# Arduino_FPGA_Top-Level_Interface.net
KiCad netlist of a schematic drawn in Altium Designer
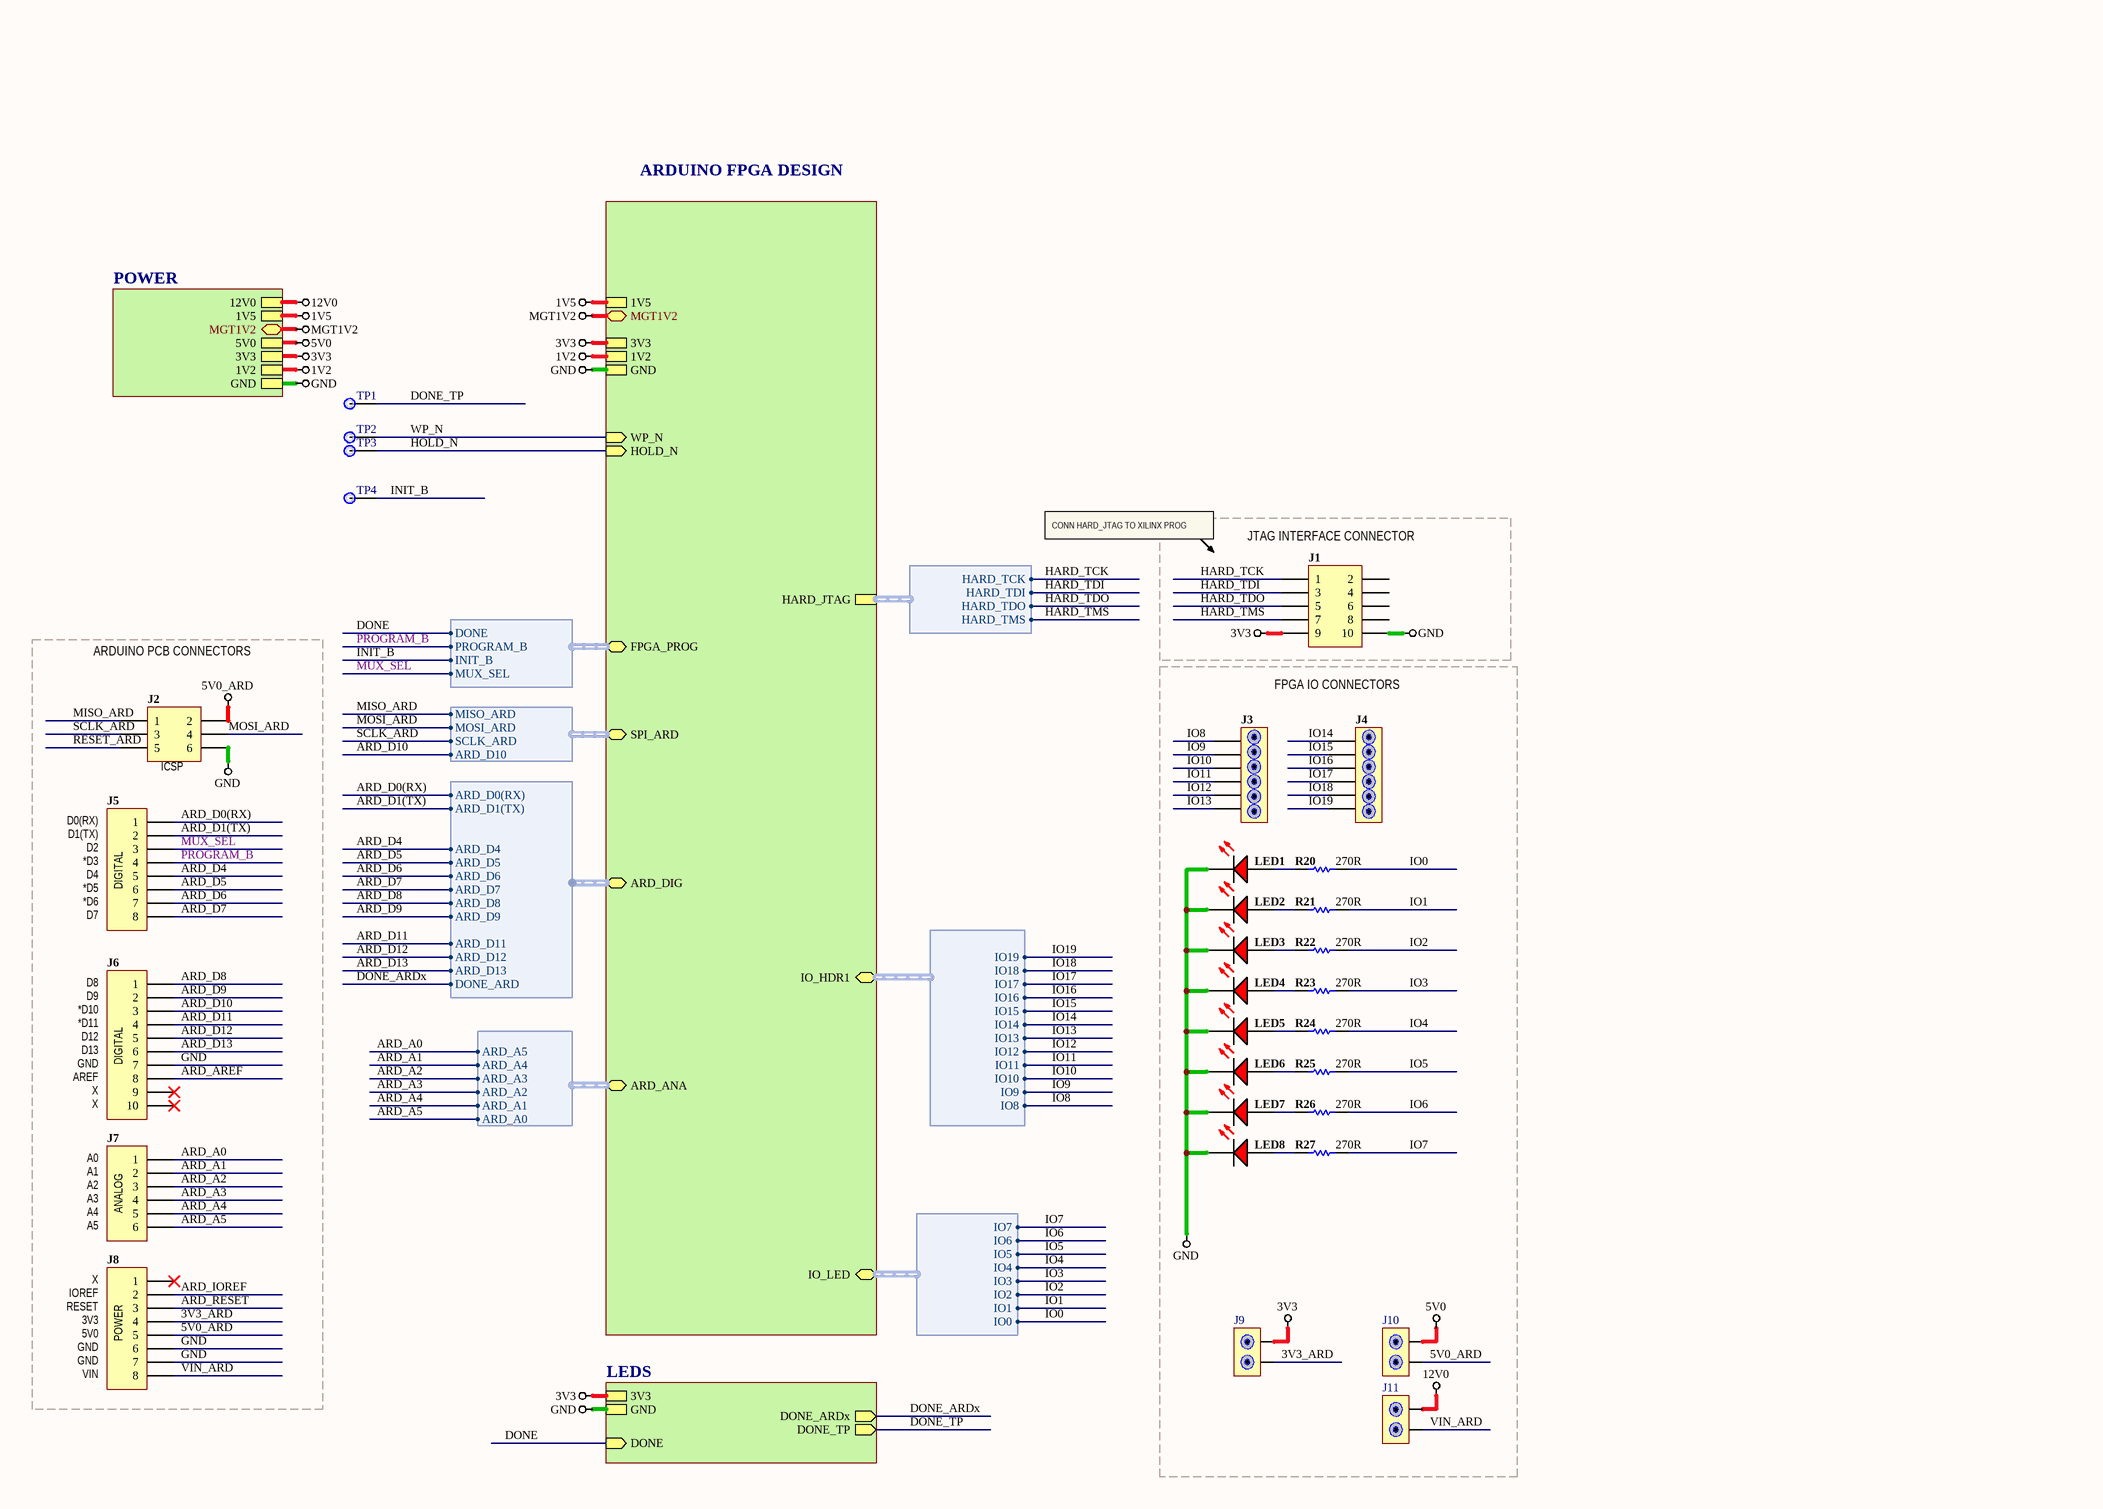
[diagram p0: Arduino FPGA Top-Level Interface.SchDoc]

(export (version "E")
  (design (tool "Eeschema 10.0.6"))
  (components
    (comp (ref "J1")
      (value "Header 5X2")
      (footprint "HDR2X5")
      (description "Header, 5-Pin, Dual row")
      (fields
        (field (name "MANUFACTURER PART NUMBER") "67997-210HLF")
        (field (name "PUBLISHER") "Altium Limited")
      )
      (libsource (lib "Miscellaneous Connectors") (part "Header 5X2"))
    )
    (comp (ref "J2")
      (value "Header 3X2")
      (footprint "2X03")
      (description "Header, 3-Pin, Dual row")
      (fields (field (name "MANUFACTURER PART NUMBER") "DNP") (field (name "PUBLISHER") "Altium Limited"))
      (libsource (lib "Miscellaneous Connectors") (part "Header 3X2"))
    )
    (comp (ref "J3")
      (value "6-POS VERTICAL HEADER")
      (footprint "HDR1X6")
      (fields (field (name "MANUFACTURER PART NUMBER") "68000-406HLF"))
      (libsource (lib "HDR1X6") (part "6-POS-HDR"))
    )
    (comp (ref "J4")
      (value "6-POS VERTICAL HEADER")
      (footprint "HDR1X6")
      (fields (field (name "MANUFACTURER PART NUMBER") "68000-406HLF"))
      (libsource (lib "HDR1X6") (part "6-POS-HDR"))
    )
    (comp (ref "J5")
      (value "Header 8")
      (footprint "1X08")
      (description "Header, 8-Pin")
      (fields (field (name "MANUFACTURER PART NUMBER") "DNP") (field (name "PUBLISHER") "Altium Limited"))
      (libsource (lib "Miscellaneous Connectors") (part "Header 8"))
    )
    (comp (ref "J6")
      (value "Header 10")
      (footprint "1X10@1")
      (description "Header, 10-Pin")
      (fields (field (name "MANUFACTURER PART NUMBER") "DNP") (field (name "PUBLISHER") "Altium Limited"))
      (libsource (lib "Miscellaneous Connectors") (part "Header 10"))
    )
    (comp (ref "J7")
      (value "Header 6")
      (footprint "1X06")
      (description "Header, 6-Pin")
      (fields (field (name "MANUFACTURER PART NUMBER") "DNP") (field (name "PUBLISHER") "Altium Limited"))
      (libsource (lib "Miscellaneous Connectors") (part "Header 6"))
    )
    (comp (ref "J8")
      (value "Header 8")
      (footprint "1X08")
      (description "Header, 8-Pin")
      (fields (field (name "MANUFACTURER PART NUMBER") "DNP") (field (name "PUBLISHER") "Altium Limited"))
      (libsource (lib "Miscellaneous Connectors") (part "Header 8"))
    )
    (comp (ref "J9")
      (value "Jumper")
      (footprint "JMP1X2")
      (description "Standard 2 Pin Jumper, 100mil spacing")
      (fields (field (name "MANUFACTURER PART NUMBER") "M20-9770246"))
      (libsource (lib "JMP1X2") (part "JMP1X2"))
    )
    (comp (ref "J10")
      (value "Jumper")
      (footprint "JMP1X2")
      (description "Standard 2 Pin Jumper, 100mil spacing")
      (fields (field (name "MANUFACTURER PART NUMBER") "M20-9770246"))
      (libsource (lib "JMP1X2") (part "JMP1X2"))
    )
    (comp (ref "J11")
      (value "Jumper")
      (footprint "JMP1X2")
      (description "Standard 2 Pin Jumper, 100mil spacing")
      (fields (field (name "MANUFACTURER PART NUMBER") "M20-9770246"))
      (libsource (lib "JMP1X2") (part "JMP1X2"))
    )
    (comp (ref "LED1")
      (value "0402-LED-RED")
      (footprint "LED_0402")
      (description "0402 LED,RED")
      (fields (field (name "MANUFACTURER PART NUMBER") "LTST-C190KRKT"))
      (libsource (lib "Component_DB") (part "LED_RED_A1K2-2"))
    )
    (comp (ref "LED2")
      (value "0402-LED-RED")
      (footprint "LED_0402")
      (description "0402 LED,RED")
      (fields (field (name "MANUFACTURER PART NUMBER") "LTST-C190KRKT"))
      (libsource (lib "Component_DB") (part "LED_RED_A1K2-2"))
    )
    (comp (ref "LED3")
      (value "0402-LED-RED")
      (footprint "LED_0402")
      (description "0402 LED,RED")
      (fields (field (name "MANUFACTURER PART NUMBER") "LTST-C190KRKT"))
      (libsource (lib "Component_DB") (part "LED_RED_A1K2-2"))
    )
    (comp (ref "LED4")
      (value "0402-LED-RED")
      (footprint "LED_0402")
      (description "0402 LED,RED")
      (fields (field (name "MANUFACTURER PART NUMBER") "LTST-C190KRKT"))
      (libsource (lib "Component_DB") (part "LED_RED_A1K2-2"))
    )
    (comp (ref "LED5")
      (value "0402-LED-RED")
      (footprint "LED_0402")
      (description "0402 LED,RED")
      (fields (field (name "MANUFACTURER PART NUMBER") "LTST-C190KRKT"))
      (libsource (lib "Component_DB") (part "LED_RED_A1K2-2"))
    )
    (comp (ref "LED6")
      (value "0402-LED-RED")
      (footprint "LED_0402")
      (description "0402 LED,RED")
      (fields (field (name "MANUFACTURER PART NUMBER") "LTST-C190KRKT"))
      (libsource (lib "Component_DB") (part "LED_RED_A1K2-2"))
    )
    (comp (ref "LED7")
      (value "0402-LED-RED")
      (footprint "LED_0402")
      (description "0402 LED,RED")
      (fields (field (name "MANUFACTURER PART NUMBER") "LTST-C190KRKT"))
      (libsource (lib "Component_DB") (part "LED_RED_A1K2-2"))
    )
    (comp (ref "LED8")
      (value "0402-LED-RED")
      (footprint "LED_0402")
      (description "0402 LED,RED")
      (fields (field (name "MANUFACTURER PART NUMBER") "LTST-C190KRKT"))
      (libsource (lib "Component_DB") (part "LED_RED_A1K2-2"))
    )
    (comp (ref "R20")
      (value "270R")
      (footprint "RESC0402(1005)40_L")
      (description "0402 (1005 Metric) 1/16 W 270R 1 Thick Film Chip Resistor")
      (fields (field (name "POWER") "1/16 W") (field (name "MANUFACTURER PART NUMBER") "RC1005F271CS"))
      (libsource (lib "Component_DB") (part "RES"))
    )
    (comp (ref "R21")
      (value "270R")
      (footprint "RESC0402(1005)40_L")
      (description "0402 (1005 Metric) 1/16 W 270R 1 Thick Film Chip Resistor")
      (fields (field (name "POWER") "1/16 W") (field (name "MANUFACTURER PART NUMBER") "RC1005F271CS"))
      (libsource (lib "Component_DB") (part "RES"))
    )
    (comp (ref "R22")
      (value "270R")
      (footprint "RESC0402(1005)40_L")
      (description "0402 (1005 Metric) 1/16 W 270R 1 Thick Film Chip Resistor")
      (fields (field (name "POWER") "1/16 W") (field (name "MANUFACTURER PART NUMBER") "RC1005F271CS"))
      (libsource (lib "Component_DB") (part "RES"))
    )
    (comp (ref "R23")
      (value "270R")
      (footprint "RESC0402(1005)40_L")
      (description "0402 (1005 Metric) 1/16 W 270R 1 Thick Film Chip Resistor")
      (fields (field (name "POWER") "1/16 W") (field (name "MANUFACTURER PART NUMBER") "RC1005F271CS"))
      (libsource (lib "Component_DB") (part "RES"))
    )
    (comp (ref "R24")
      (value "270R")
      (footprint "RESC0402(1005)40_L")
      (description "0402 (1005 Metric) 1/16 W 270R 1 Thick Film Chip Resistor")
      (fields (field (name "POWER") "1/16 W") (field (name "MANUFACTURER PART NUMBER") "RC1005F271CS"))
      (libsource (lib "Component_DB") (part "RES"))
    )
    (comp (ref "R25")
      (value "270R")
      (footprint "RESC0402(1005)40_L")
      (description "0402 (1005 Metric) 1/16 W 270R 1 Thick Film Chip Resistor")
      (fields (field (name "POWER") "1/16 W") (field (name "MANUFACTURER PART NUMBER") "RC1005F271CS"))
      (libsource (lib "Component_DB") (part "RES"))
    )
    (comp (ref "R26")
      (value "270R")
      (footprint "RESC0402(1005)40_L")
      (description "0402 (1005 Metric) 1/16 W 270R 1 Thick Film Chip Resistor")
      (fields (field (name "POWER") "1/16 W") (field (name "MANUFACTURER PART NUMBER") "RC1005F271CS"))
      (libsource (lib "Component_DB") (part "RES"))
    )
    (comp (ref "R27")
      (value "270R")
      (footprint "RESC0402(1005)40_L")
      (description "0402 (1005 Metric) 1/16 W 270R 1 Thick Film Chip Resistor")
      (fields (field (name "POWER") "1/16 W") (field (name "MANUFACTURER PART NUMBER") "RC1005F271CS"))
      (libsource (lib "Component_DB") (part "RES"))
    )
    (comp (ref "TP1")
      (value "TESTPOINT_TH")
      (footprint "TESTPOINT_TH")
      (fields (field (name "MANUFACTURER PART NUMBER") "TESTPOINT"))
      (libsource (lib "TESTPOINT_TH") (part "TESTPOINT_TH"))
    )
    (comp (ref "TP2")
      (value "TESTPOINT_TH")
      (footprint "TESTPOINT_TH")
      (fields (field (name "MANUFACTURER PART NUMBER") "TESTPOINT"))
      (libsource (lib "TESTPOINT_TH") (part "TESTPOINT_TH"))
    )
    (comp (ref "TP3")
      (value "TESTPOINT_TH")
      (footprint "TESTPOINT_TH")
      (fields (field (name "MANUFACTURER PART NUMBER") "TESTPOINT"))
      (libsource (lib "TESTPOINT_TH") (part "TESTPOINT_TH"))
    )
    (comp (ref "TP4")
      (value "TESTPOINT_TH")
      (footprint "TESTPOINT_TH")
      (fields (field (name "MANUFACTURER PART NUMBER") "TESTPOINT"))
      (libsource (lib "TESTPOINT_TH") (part "TESTPOINT_TH"))
    )
  )
  (nets
    (net (code "8") (name "/3V3_ARD") (class "Default")
      (node (ref "J8") (pin "4") (pinfunction "4_4") (pintype "passive"))
      (node (ref "J9") (pin "1") (pinfunction "1_1") (pintype "passive"))
    )
    (net (code "9") (name "/ARD_A0") (class "Default")
      (node (ref "J7") (pin "1") (pinfunction "1_1") (pintype "passive"))
    )
    (net (code "10") (name "/ARD_A1") (class "Default")
      (node (ref "J7") (pin "2") (pinfunction "2_2") (pintype "passive"))
    )
    (net (code "11") (name "/ARD_A2") (class "Default")
      (node (ref "J7") (pin "3") (pinfunction "3_3") (pintype "passive"))
    )
    (net (code "12") (name "/ARD_A3") (class "Default")
      (node (ref "J7") (pin "4") (pinfunction "4_4") (pintype "passive"))
    )
    (net (code "13") (name "/ARD_A4") (class "Default")
      (node (ref "J7") (pin "5") (pinfunction "5_5") (pintype "passive"))
    )
    (net (code "14") (name "/ARD_A5") (class "Default")
      (node (ref "J7") (pin "6") (pinfunction "6_6") (pintype "passive"))
    )
    (net (code "15") (name "/ARD_AREF") (class "Default")
      (node (ref "J6") (pin "8") (pinfunction "8_8") (pintype "passive"))
    )
    (net (code "16") (name "/ARD_D0(RX)") (class "Default")
      (node (ref "J5") (pin "1") (pinfunction "1_1") (pintype "passive"))
    )
    (net (code "17") (name "/ARD_D1(TX)") (class "Default")
      (node (ref "J5") (pin "2") (pinfunction "2_2") (pintype "passive"))
    )
    (net (code "18") (name "/ARD_D4") (class "Default")
      (node (ref "J5") (pin "5") (pinfunction "5_5") (pintype "passive"))
    )
    (net (code "19") (name "/ARD_D5") (class "Default")
      (node (ref "J5") (pin "6") (pinfunction "6_6") (pintype "passive"))
    )
    (net (code "20") (name "/ARD_D6") (class "Default")
      (node (ref "J5") (pin "7") (pinfunction "7_7") (pintype "passive"))
    )
    (net (code "21") (name "/ARD_D7") (class "Default")
      (node (ref "J5") (pin "8") (pinfunction "8_8") (pintype "passive"))
    )
    (net (code "22") (name "/ARD_D8") (class "Default")
      (node (ref "J6") (pin "1") (pinfunction "1_1") (pintype "passive"))
    )
    (net (code "23") (name "/ARD_D9") (class "Default")
      (node (ref "J6") (pin "2") (pinfunction "2_2") (pintype "passive"))
    )
    (net (code "24") (name "/ARD_D10") (class "Default")
      (node (ref "J6") (pin "3") (pinfunction "3_3") (pintype "passive"))
    )
    (net (code "25") (name "/ARD_D11") (class "Default")
      (node (ref "J6") (pin "4") (pinfunction "4_4") (pintype "passive"))
    )
    (net (code "26") (name "/ARD_D12") (class "Default")
      (node (ref "J6") (pin "5") (pinfunction "5_5") (pintype "passive"))
    )
    (net (code "27") (name "/ARD_D13") (class "Default")
      (node (ref "J6") (pin "6") (pinfunction "6_6") (pintype "passive"))
    )
    (net (code "28") (name "/ARD_IOREF") (class "Default")
      (node (ref "J8") (pin "2") (pinfunction "2_2") (pintype "passive"))
    )
    (net (code "29") (name "/ARD_RESET") (class "Default")
      (node (ref "J8") (pin "3") (pinfunction "3_3") (pintype "passive"))
    )
    (net (code "32") (name "/DONE_TP") (class "Default")
      (node (ref "TP1") (pin "1") (pinfunction "1_1") (pintype "passive"))
    )
    (net (code "33") (name "/HARD_TCK") (class "Default")
      (node (ref "J1") (pin "1") (pinfunction "1_1") (pintype "passive"))
    )
    (net (code "34") (name "/HARD_TDI") (class "Default")
      (node (ref "J1") (pin "3") (pinfunction "3_3") (pintype "passive"))
    )
    (net (code "35") (name "/HARD_TDO") (class "Default")
      (node (ref "J1") (pin "5") (pinfunction "5_5") (pintype "passive"))
    )
    (net (code "36") (name "/HARD_TMS") (class "Default")
      (node (ref "J1") (pin "7") (pinfunction "7_7") (pintype "passive"))
    )
    (net (code "37") (name "/HOLD_N") (class "Default")
      (node (ref "TP3") (pin "1") (pinfunction "1_1") (pintype "passive"))
    )
    (net (code "38") (name "/INIT_B") (class "Default")
      (node (ref "TP4") (pin "1") (pinfunction "1_1") (pintype "passive"))
    )
    (net (code "39") (name "/IO0") (class "Default")
      (node (ref "R20") (pin "2") (pinfunction "2_2") (pintype "passive"))
    )
    (net (code "40") (name "/IO1") (class "Default")
      (node (ref "R21") (pin "2") (pinfunction "2_2") (pintype "passive"))
    )
    (net (code "41") (name "/IO2") (class "Default")
      (node (ref "R22") (pin "2") (pinfunction "2_2") (pintype "passive"))
    )
    (net (code "42") (name "/IO3") (class "Default")
      (node (ref "R23") (pin "2") (pinfunction "2_2") (pintype "passive"))
    )
    (net (code "43") (name "/IO4") (class "Default")
      (node (ref "R24") (pin "2") (pinfunction "2_2") (pintype "passive"))
    )
    (net (code "44") (name "/IO5") (class "Default")
      (node (ref "R25") (pin "2") (pinfunction "2_2") (pintype "passive"))
    )
    (net (code "45") (name "/IO6") (class "Default")
      (node (ref "R26") (pin "2") (pinfunction "2_2") (pintype "passive"))
    )
    (net (code "46") (name "/IO7") (class "Default")
      (node (ref "R27") (pin "2") (pinfunction "2_2") (pintype "passive"))
    )
    (net (code "47") (name "/IO8") (class "Default")
      (node (ref "J3") (pin "1") (pinfunction "1_1") (pintype "passive"))
    )
    (net (code "48") (name "/IO9") (class "Default")
      (node (ref "J3") (pin "2") (pinfunction "2_2") (pintype "passive"))
    )
    (net (code "49") (name "/IO10") (class "Default")
      (node (ref "J3") (pin "3") (pinfunction "3_3") (pintype "passive"))
    )
    (net (code "50") (name "/IO11") (class "Default")
      (node (ref "J3") (pin "4") (pinfunction "4_4") (pintype "passive"))
    )
    (net (code "51") (name "/IO12") (class "Default")
      (node (ref "J3") (pin "5") (pinfunction "5_5") (pintype "passive"))
    )
    (net (code "52") (name "/IO13") (class "Default")
      (node (ref "J3") (pin "6") (pinfunction "6_6") (pintype "passive"))
    )
    (net (code "53") (name "/IO14") (class "Default")
      (node (ref "J4") (pin "1") (pinfunction "1_1") (pintype "passive"))
    )
    (net (code "54") (name "/IO15") (class "Default")
      (node (ref "J4") (pin "2") (pinfunction "2_2") (pintype "passive"))
    )
    (net (code "55") (name "/IO16") (class "Default")
      (node (ref "J4") (pin "3") (pinfunction "3_3") (pintype "passive"))
    )
    (net (code "56") (name "/IO17") (class "Default")
      (node (ref "J4") (pin "4") (pinfunction "4_4") (pintype "passive"))
    )
    (net (code "57") (name "/IO18") (class "Default")
      (node (ref "J4") (pin "5") (pinfunction "5_5") (pintype "passive"))
    )
    (net (code "58") (name "/IO19") (class "Default")
      (node (ref "J4") (pin "6") (pinfunction "6_6") (pintype "passive"))
    )
    (net (code "59") (name "/MISO_ARD") (class "Default")
      (node (ref "J2") (pin "1") (pinfunction "1_1") (pintype "passive"))
    )
    (net (code "60") (name "/MOSI_ARD") (class "Default")
      (node (ref "J2") (pin "4") (pinfunction "4_4") (pintype "passive"))
    )
    (net (code "61") (name "/MUX_SEL") (class "Default")
      (node (ref "J5") (pin "3") (pinfunction "3_3") (pintype "passive"))
    )
    (net (code "62") (name "/PROGRAM_B") (class "Default")
      (node (ref "J5") (pin "4") (pinfunction "4_4") (pintype "passive"))
    )
    (net (code "63") (name "/RESET_ARD") (class "Default")
      (node (ref "J2") (pin "5") (pinfunction "5_5") (pintype "passive"))
    )
    (net (code "64") (name "/SCLK_ARD") (class "Default")
      (node (ref "J2") (pin "3") (pinfunction "3_3") (pintype "passive"))
    )
    (net (code "65") (name "/VIN_ARD") (class "Default")
      (node (ref "J11") (pin "1") (pinfunction "1_1") (pintype "passive"))
      (node (ref "J8") (pin "8") (pinfunction "8_8") (pintype "passive"))
    )
    (net (code "66") (name "/WP_N") (class "Default")
      (node (ref "TP2") (pin "1") (pinfunction "1_1") (pintype "passive"))
    )
    (net (code "76") (name "3V3") (class "Default")
      (node (ref "J1") (pin "9") (pinfunction "9_9") (pintype "passive"))
      (node (ref "J9") (pin "2") (pinfunction "2_2") (pintype "passive"))
    )
    (net (code "77") (name "5V0") (class "Default")
      (node (ref "J10") (pin "2") (pinfunction "2_2") (pintype "passive"))
    )
    (net (code "78") (name "5V0_ARD") (class "Default")
      (node (ref "J10") (pin "1") (pinfunction "1_1") (pintype "passive"))
      (node (ref "J8") (pin "5") (pinfunction "5_5") (pintype "passive"))
    )
    (net (code "79") (name "12V0") (class "Default")
      (node (ref "J11") (pin "2") (pinfunction "2_2") (pintype "passive"))
    )
    (net (code "80") (name "GND") (class "Default")
      (node (ref "J1") (pin "10") (pinfunction "10_10") (pintype "passive"))
      (node (ref "J2") (pin "6") (pinfunction "6_6") (pintype "passive"))
      (node (ref "J6") (pin "7") (pinfunction "7_7") (pintype "passive"))
      (node (ref "J8") (pin "6") (pinfunction "6_6") (pintype "passive"))
      (node (ref "J8") (pin "7") (pinfunction "7_7") (pintype "passive"))
      (node (ref "LED1") (pin "2") (pinfunction "K_2") (pintype "passive"))
      (node (ref "LED2") (pin "2") (pinfunction "K_2") (pintype "passive"))
      (node (ref "LED3") (pin "2") (pinfunction "K_2") (pintype "passive"))
      (node (ref "LED4") (pin "2") (pinfunction "K_2") (pintype "passive"))
      (node (ref "LED5") (pin "2") (pinfunction "K_2") (pintype "passive"))
      (node (ref "LED6") (pin "2") (pinfunction "K_2") (pintype "passive"))
      (node (ref "LED7") (pin "2") (pinfunction "K_2") (pintype "passive"))
      (node (ref "LED8") (pin "2") (pinfunction "K_2") (pintype "passive"))
    )
    (net (code "82") (name "Net-(LED1-A)") (class "Default")
      (node (ref "LED1") (pin "1") (pinfunction "A_1") (pintype "passive"))
      (node (ref "R20") (pin "1") (pinfunction "1_1") (pintype "passive"))
    )
    (net (code "83") (name "Net-(LED2-A)") (class "Default")
      (node (ref "LED2") (pin "1") (pinfunction "A_1") (pintype "passive"))
      (node (ref "R21") (pin "1") (pinfunction "1_1") (pintype "passive"))
    )
    (net (code "84") (name "Net-(LED3-A)") (class "Default")
      (node (ref "LED3") (pin "1") (pinfunction "A_1") (pintype "passive"))
      (node (ref "R22") (pin "1") (pinfunction "1_1") (pintype "passive"))
    )
    (net (code "85") (name "Net-(LED4-A)") (class "Default")
      (node (ref "LED4") (pin "1") (pinfunction "A_1") (pintype "passive"))
      (node (ref "R23") (pin "1") (pinfunction "1_1") (pintype "passive"))
    )
    (net (code "86") (name "Net-(LED5-A)") (class "Default")
      (node (ref "LED5") (pin "1") (pinfunction "A_1") (pintype "passive"))
      (node (ref "R24") (pin "1") (pinfunction "1_1") (pintype "passive"))
    )
    (net (code "87") (name "Net-(LED6-A)") (class "Default")
      (node (ref "LED6") (pin "1") (pinfunction "A_1") (pintype "passive"))
      (node (ref "R25") (pin "1") (pinfunction "1_1") (pintype "passive"))
    )
    (net (code "88") (name "Net-(LED7-A)") (class "Default")
      (node (ref "LED7") (pin "1") (pinfunction "A_1") (pintype "passive"))
      (node (ref "R26") (pin "1") (pinfunction "1_1") (pintype "passive"))
    )
    (net (code "89") (name "Net-(LED8-A)") (class "Default")
      (node (ref "LED8") (pin "1") (pinfunction "A_1") (pintype "passive"))
      (node (ref "R27") (pin "1") (pinfunction "1_1") (pintype "passive"))
    )
    (net (code "90") (name "unconnected-(J1-Pad2)") (class "Default")
      (node (ref "J1") (pin "2") (pinfunction "2_2") (pintype "passive"))
    )
    (net (code "91") (name "unconnected-(J1-Pad4)") (class "Default")
      (node (ref "J1") (pin "4") (pinfunction "4_4") (pintype "passive"))
    )
    (net (code "92") (name "unconnected-(J1-Pad6)") (class "Default")
      (node (ref "J1") (pin "6") (pinfunction "6_6") (pintype "passive"))
    )
    (net (code "93") (name "unconnected-(J1-Pad8)") (class "Default")
      (node (ref "J1") (pin "8") (pinfunction "8_8") (pintype "passive"))
    )
    (net (code "94") (name "unconnected-(J2-Pad2)") (class "Default")
      (node (ref "J2") (pin "2") (pinfunction "2_2") (pintype "passive"))
    )
    (net (code "95") (name "unconnected-(J6-Pad9)") (class "Default")
      (node (ref "J6") (pin "9") (pinfunction "9_9") (pintype "passive+no_connect"))
    )
    (net (code "96") (name "unconnected-(J6-Pad10)") (class "Default")
      (node (ref "J6") (pin "10") (pinfunction "10_10") (pintype "passive+no_connect"))
    )
    (net (code "97") (name "unconnected-(J8-Pad1)") (class "Default")
      (node (ref "J8") (pin "1") (pinfunction "1_1") (pintype "passive+no_connect"))
    )
  )
)
